# Connectors_2.net
KiCad netlist of a schematic drawn in Altium Designer
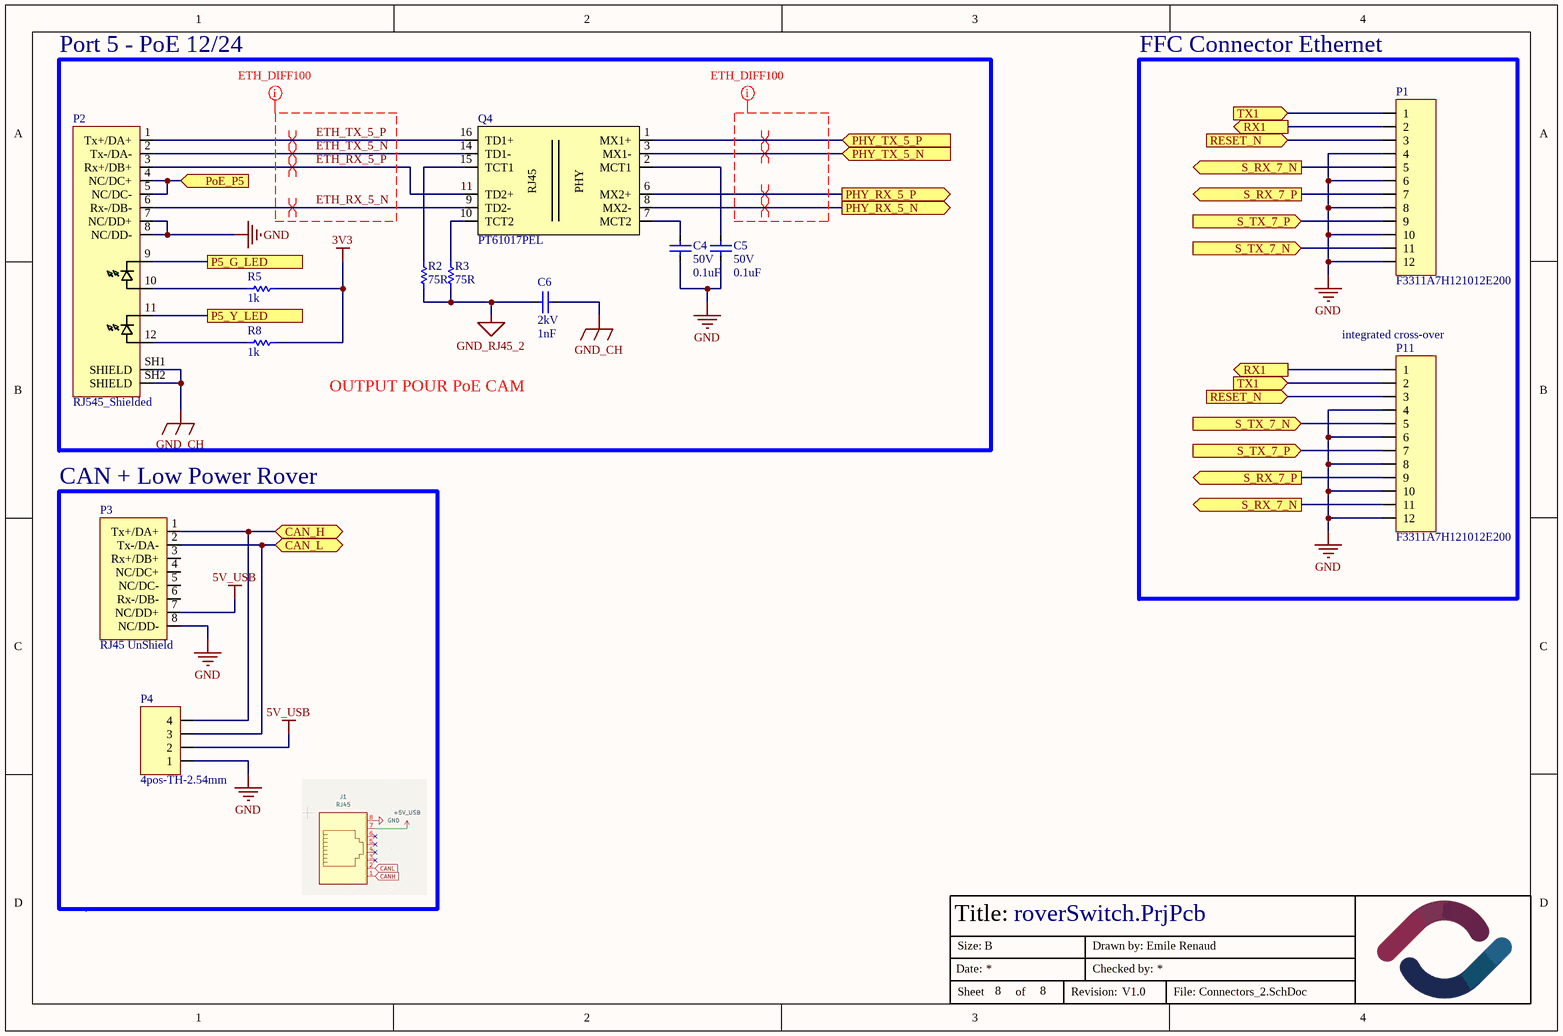
[diagram p0: Connectors_2.SchDoc]

(export (version "E")
  (design (tool "Eeschema 10.0.6"))
  (components
    (comp (ref "C4")
      (value "0.1uF")
      (footprint "CAPACITOR-0603")
      (description "Capacitor-0603-0.1uF-50V-X7R")
      (fields (field (name "VOLT") "50V"))
      (libsource (lib "Capacitors") (part "Capacitor-0603-0.1uF-50V-X7R"))
    )
    (comp (ref "C5")
      (value "0.1uF")
      (footprint "CAPACITOR-0603")
      (description "Capacitor-0603-0.1uF-50V-X7R")
      (fields (field (name "VOLT") "50V"))
      (libsource (lib "Capacitors") (part "Capacitor-0603-0.1uF-50V-X7R"))
    )
    (comp (ref "C6")
      (value "1nF")
      (footprint "CAPACITOR-1206")
      (description "Capacitor-1206-1nF-2kV-X7R")
      (fields (field (name "VOLT") "2kV"))
      (libsource (lib "Capacitors") (part "Capacitor-1206-1nF-2kV-X7R"))
    )
    (comp (ref "P1")
      (value "F3311A7H121012E200")
      (footprint "AMPHENOL_F3311A7H121012E200")
      (description "CONN FFC FPC 12POS 0.5MM R/A")
      (libsource (lib "FFC_connector") (part "FFC-12P-0.5MM-R/A"))
    )
    (comp (ref "P2")
      (value "RJ545_Shielded")
      (footprint "ADAMTECH_MTJ-88ARX1-FSM-LG")
      (description "Jack Modular Connector 8p8c (RJ45, Ethernet) 90° Angle (Right) Shielded with LEDs")
      (libsource (lib "PC-connector") (part "RJ545_Shielded"))
    )
    (comp (ref "P3")
      (value "RJ45 UnShield")
      (footprint "AMPHENOL_54602-908LF")
      (description "Jack Modular Connector 8p8c (RJ45, Ethernet) 90° Angle (Right) Unshielded Cat3")
      (libsource (lib "PC-connector") (part "RJ545"))
    )
    (comp (ref "P4")
      (value "4pos-TH-2.54mm")
      (footprint "HDR1X4")
      (description "4pos TH 2.54mm Header")
      (libsource (lib "Header") (part "4pos-TH-2.54mm"))
    )
    (comp (ref "P11")
      (value "F3311A7H121012E200")
      (footprint "AMPHENOL_F3311A7H121012E200")
      (description "CONN FFC FPC 12POS 0.5MM R/A")
      (libsource (lib "FFC_connector") (part "FFC-12P-0.5MM-R/A"))
    )
    (comp (ref "Q4")
      (value "PT61017PEL")
      (footprint "SOIC_PT61017PEL")
      (description "350µH LAN 10/100 Base-T Pulse Transformer 1CT:1CT Surface Mount")
      (libsource (lib "Transformers-Magnetics") (part "PT61017PEL"))
    )
    (comp (ref "R2")
      (value "75R")
      (footprint "Resistor-0603")
      (description "Resistor0603-75R")
      (fields (field (name "Comment") "SMT resistor"))
      (libsource (lib "Resistors") (part "Resistor-0603-75R"))
    )
    (comp (ref "R3")
      (value "75R")
      (footprint "Resistor-0603")
      (description "Resistor0603-75R")
      (fields (field (name "Comment") "SMT resistor"))
      (libsource (lib "Resistors") (part "Resistor-0603-75R"))
    )
    (comp (ref "R5")
      (value "1k")
      (footprint "Resistor-0603")
      (description "Resistor0603-1k")
      (fields (field (name "Comment") "SMT resistor"))
      (libsource (lib "Resistors") (part "Resistor-0603-1k"))
    )
    (comp (ref "R8")
      (value "1k")
      (footprint "Resistor-0603")
      (description "Resistor0603-1k")
      (fields (field (name "Comment") "SMT resistor"))
      (libsource (lib "Resistors") (part "Resistor-0603-1k"))
    )
  )
  (nets
    (net (code "1") (name "/CAN_H") (class "Default")
      (node (ref "P3") (pin "1") (pinfunction "Tx+/DA+_1") (pintype "passive"))
      (node (ref "P4") (pin "4") (pinfunction "4_4") (pintype "passive"))
    )
    (net (code "2") (name "/CAN_L") (class "Default")
      (node (ref "P3") (pin "2") (pinfunction "Tx-/DA-_2") (pintype "passive"))
      (node (ref "P4") (pin "3") (pinfunction "3_3") (pintype "passive"))
    )
    (net (code "3") (name "/ETH_RX_5_N") (class "Default")
      (node (ref "P2") (pin "6") (pinfunction "Rx-/DB-_6") (pintype "passive"))
      (node (ref "Q4") (pin "9") (pinfunction "TD2-_9") (pintype "passive"))
    )
    (net (code "4") (name "/ETH_RX_5_P") (class "Default")
      (node (ref "P2") (pin "3") (pinfunction "Rx+/DB+_3") (pintype "passive"))
      (node (ref "Q4") (pin "11") (pinfunction "TD2+_11") (pintype "passive"))
    )
    (net (code "5") (name "/ETH_TX_5_N") (class "Default")
      (node (ref "P2") (pin "2") (pinfunction "Tx-/DA-_2") (pintype "passive"))
      (node (ref "Q4") (pin "14") (pinfunction "TD1-_14") (pintype "passive"))
    )
    (net (code "6") (name "/ETH_TX_5_P") (class "Default")
      (node (ref "P2") (pin "1") (pinfunction "Tx+/DA+_1") (pintype "passive"))
      (node (ref "Q4") (pin "16") (pinfunction "TD1+_16") (pintype "passive"))
    )
    (net (code "7") (name "/P5_G_LED") (class "Default")
      (node (ref "P2") (pin "9") (pinfunction "9_9") (pintype "passive"))
    )
    (net (code "8") (name "/P5_Y_LED") (class "Default")
      (node (ref "P2") (pin "11") (pinfunction "11_11") (pintype "passive"))
    )
    (net (code "9") (name "/PHY_RX_5_N") (class "Default")
      (node (ref "Q4") (pin "8") (pinfunction "MX2-_8") (pintype "passive"))
    )
    (net (code "10") (name "/PHY_RX_5_P") (class "Default")
      (node (ref "Q4") (pin "6") (pinfunction "MX2+_6") (pintype "passive"))
    )
    (net (code "11") (name "/PHY_TX_5_N") (class "Default")
      (node (ref "Q4") (pin "3") (pinfunction "MX1-_3") (pintype "passive"))
    )
    (net (code "12") (name "/PHY_TX_5_P") (class "Default")
      (node (ref "Q4") (pin "1") (pinfunction "MX1+_1") (pintype "passive"))
    )
    (net (code "13") (name "/PoE_P5") (class "Default")
      (node (ref "P2") (pin "4") (pinfunction "NC/DC+_4") (pintype "passive"))
      (node (ref "P2") (pin "5") (pinfunction "NC/DC-_5") (pintype "passive"))
    )
    (net (code "14") (name "/RESET_N") (class "Default")
      (node (ref "P1") (pin "3") (pinfunction "3_3") (pintype "passive"))
      (node (ref "P11") (pin "3") (pinfunction "3_3") (pintype "passive"))
    )
    (net (code "15") (name "/RX1") (class "Default")
      (node (ref "P1") (pin "2") (pinfunction "2_2") (pintype "passive"))
      (node (ref "P11") (pin "1") (pinfunction "1_1") (pintype "passive"))
    )
    (net (code "16") (name "/S_RX_7_N") (class "Default")
      (node (ref "P1") (pin "5") (pinfunction "5_5") (pintype "passive"))
      (node (ref "P11") (pin "11") (pinfunction "11_11") (pintype "passive"))
    )
    (net (code "17") (name "/S_RX_7_P") (class "Default")
      (node (ref "P1") (pin "7") (pinfunction "7_7") (pintype "passive"))
      (node (ref "P11") (pin "9") (pinfunction "9_9") (pintype "passive"))
    )
    (net (code "18") (name "/S_TX_7_N") (class "Default")
      (node (ref "P1") (pin "11") (pinfunction "11_11") (pintype "passive"))
      (node (ref "P11") (pin "5") (pinfunction "5_5") (pintype "passive"))
    )
    (net (code "19") (name "/S_TX_7_P") (class "Default")
      (node (ref "P1") (pin "9") (pinfunction "9_9") (pintype "passive"))
      (node (ref "P11") (pin "7") (pinfunction "7_7") (pintype "passive"))
    )
    (net (code "20") (name "/TX1") (class "Default")
      (node (ref "P1") (pin "1") (pinfunction "1_1") (pintype "passive"))
      (node (ref "P11") (pin "2") (pinfunction "2_2") (pintype "passive"))
    )
    (net (code "21") (name "3V3") (class "Default")
      (node (ref "R5") (pin "1") (pinfunction "1_1") (pintype "passive"))
      (node (ref "R8") (pin "1") (pinfunction "1_1") (pintype "passive"))
    )
    (net (code "22") (name "5V_USB") (class "Default")
      (node (ref "P3") (pin "7") (pinfunction "NC/DD+_7") (pintype "passive"))
      (node (ref "P4") (pin "2") (pinfunction "2_2") (pintype "passive"))
    )
    (net (code "23") (name "GND") (class "Default")
      (node (ref "C4") (pin "1") (pinfunction "1_1") (pintype "passive"))
      (node (ref "C5") (pin "1") (pinfunction "1_1") (pintype "passive"))
      (node (ref "P1") (pin "10") (pinfunction "10_10") (pintype "passive"))
      (node (ref "P1") (pin "12") (pinfunction "12_12") (pintype "passive"))
      (node (ref "P1") (pin "4") (pinfunction "4_4") (pintype "passive"))
      (node (ref "P1") (pin "6") (pinfunction "6_6") (pintype "passive"))
      (node (ref "P1") (pin "8") (pinfunction "8_8") (pintype "passive"))
      (node (ref "P11") (pin "10") (pinfunction "10_10") (pintype "passive"))
      (node (ref "P11") (pin "12") (pinfunction "12_12") (pintype "passive"))
      (node (ref "P11") (pin "4") (pinfunction "4_4") (pintype "passive"))
      (node (ref "P11") (pin "6") (pinfunction "6_6") (pintype "passive"))
      (node (ref "P11") (pin "8") (pinfunction "8_8") (pintype "passive"))
      (node (ref "P2") (pin "7") (pinfunction "NC/DD+_7") (pintype "passive"))
      (node (ref "P2") (pin "8") (pinfunction "NC/DD-_8") (pintype "passive"))
      (node (ref "P3") (pin "8") (pinfunction "NC/DD-_8") (pintype "passive"))
      (node (ref "P4") (pin "1") (pinfunction "1_1") (pintype "passive"))
    )
    (net (code "24") (name "GND_CH") (class "Default")
      (node (ref "C6") (pin "2") (pinfunction "2_2") (pintype "passive"))
      (node (ref "P2") (pin "SH1") (pinfunction "SHIELD_SH1") (pintype "passive"))
      (node (ref "P2") (pin "SH2") (pinfunction "SHIELD_SH2") (pintype "passive"))
    )
    (net (code "25") (name "GND_RJ45_2") (class "Default")
      (node (ref "C6") (pin "1") (pinfunction "1_1") (pintype "passive"))
      (node (ref "R2") (pin "1") (pinfunction "1_1") (pintype "passive"))
      (node (ref "R3") (pin "1") (pinfunction "1_1") (pintype "passive"))
    )
    (net (code "26") (name "Net-(P2-Pad10)") (class "Default")
      (node (ref "P2") (pin "10") (pinfunction "10_10") (pintype "passive"))
      (node (ref "R5") (pin "2") (pinfunction "2_2") (pintype "passive"))
    )
    (net (code "27") (name "Net-(P2-Pad12)") (class "Default")
      (node (ref "P2") (pin "12") (pinfunction "12_12") (pintype "passive"))
      (node (ref "R8") (pin "2") (pinfunction "2_2") (pintype "passive"))
    )
    (net (code "28") (name "Net-(Q4-MCT1)") (class "Default")
      (node (ref "C5") (pin "2") (pinfunction "2_2") (pintype "passive"))
      (node (ref "Q4") (pin "2") (pinfunction "MCT1_2") (pintype "passive"))
    )
    (net (code "29") (name "Net-(Q4-MCT2)") (class "Default")
      (node (ref "C4") (pin "2") (pinfunction "2_2") (pintype "passive"))
      (node (ref "Q4") (pin "7") (pinfunction "MCT2_7") (pintype "passive"))
    )
    (net (code "30") (name "Net-(Q4-TCT1)") (class "Default")
      (node (ref "Q4") (pin "15") (pinfunction "TCT1_15") (pintype "passive"))
      (node (ref "R2") (pin "2") (pinfunction "2_2") (pintype "passive"))
    )
    (net (code "31") (name "Net-(Q4-TCT2)") (class "Default")
      (node (ref "Q4") (pin "10") (pinfunction "TCT2_10") (pintype "passive"))
      (node (ref "R3") (pin "2") (pinfunction "2_2") (pintype "passive"))
    )
    (net (code "32") (name "unconnected-(P3-NC{slash}DC+-Pad4)") (class "Default")
      (node (ref "P3") (pin "4") (pinfunction "NC/DC+_4") (pintype "passive"))
    )
    (net (code "33") (name "unconnected-(P3-NC{slash}DC--Pad5)") (class "Default")
      (node (ref "P3") (pin "5") (pinfunction "NC/DC-_5") (pintype "passive"))
    )
    (net (code "34") (name "unconnected-(P3-Rx+{slash}DB+-Pad3)") (class "Default")
      (node (ref "P3") (pin "3") (pinfunction "Rx+/DB+_3") (pintype "passive"))
    )
    (net (code "35") (name "unconnected-(P3-Rx-{slash}DB--Pad6)") (class "Default")
      (node (ref "P3") (pin "6") (pinfunction "Rx-/DB-_6") (pintype "passive"))
    )
  )
)
